# 6_Magnetorquer_Drivers.net
KiCad netlist of a schematic drawn in Altium Designer
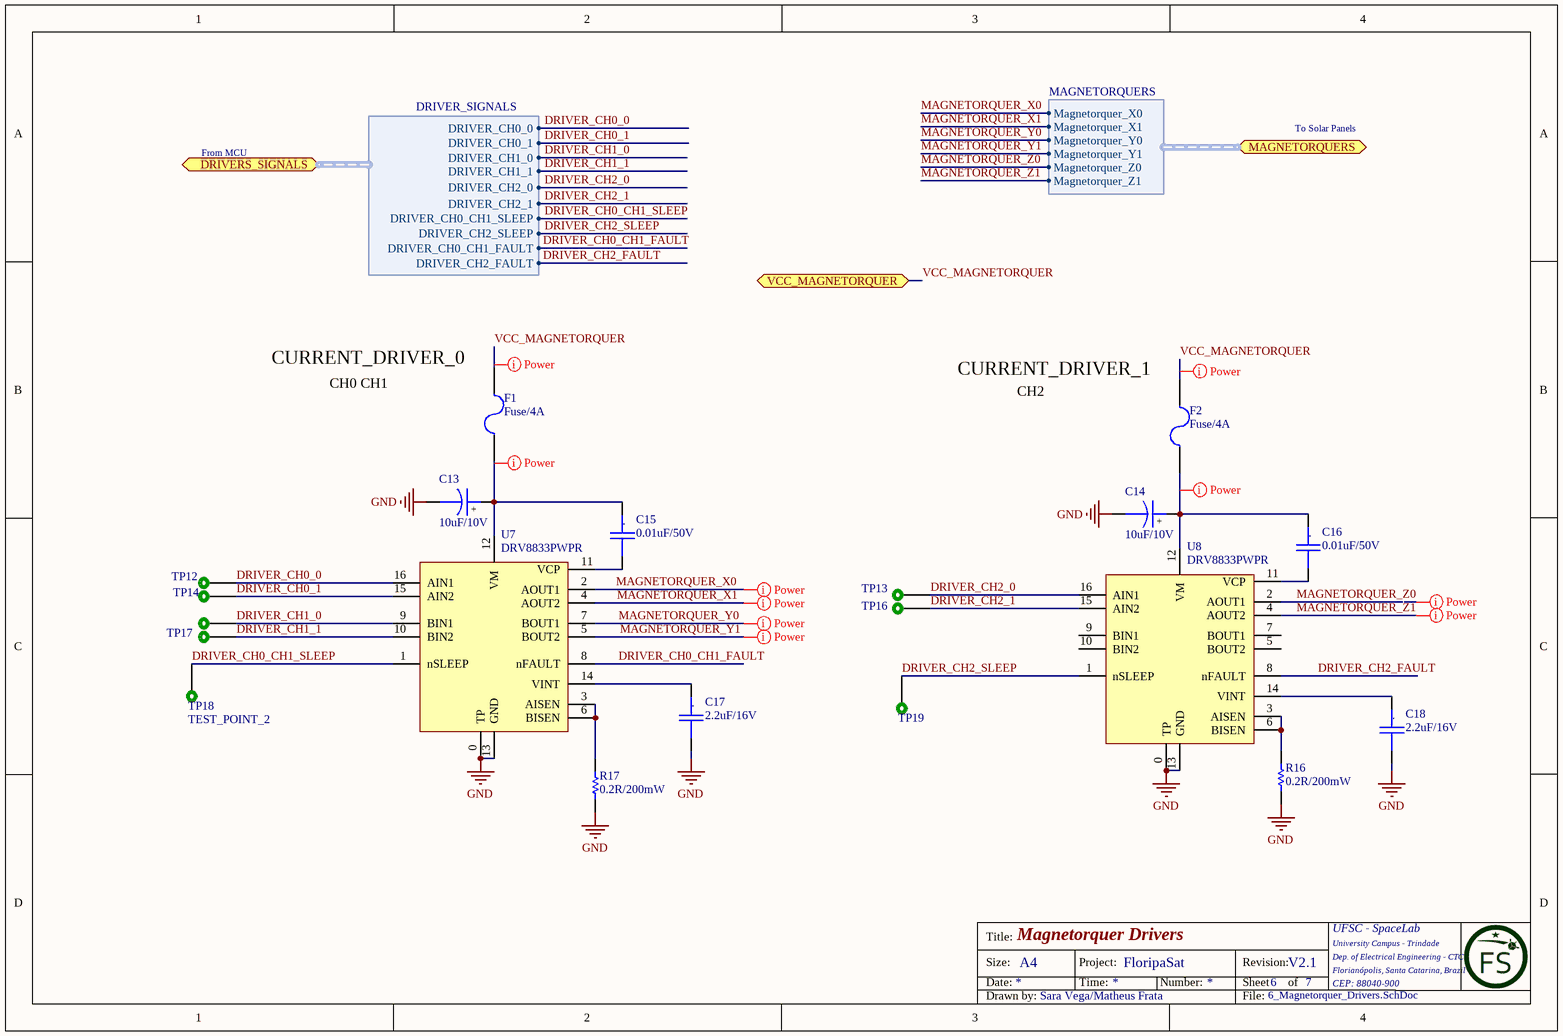
[diagram p0: 6_Magnetorquer_Drivers.SchDoc]

(export (version "E")
  (design (tool "Eeschema 10.0.6"))
  (components
    (comp (ref "C13")
      (value "10uF/10V")
      (footprint "FloripaSatPcbLib:CC0805_Tantalum")
      (description "CAP Tantalum 10uF 10V 20% 0805")
      (fields (field (name "PARTNUMBER") "TPSP106M010R2000"))
      (libsource (lib "FloripaSatSchlib") (part "Cap_Tant_SMD_10uF_10V_0805"))
    )
    (comp (ref "C14")
      (value "10uF/10V")
      (footprint "FloripaSatPcbLib:CC0805_Tantalum")
      (description "CAP Tantalum 10uF 10V 20% 0805")
      (fields (field (name "PARTNUMBER") "TPSP106M010R2000"))
      (libsource (lib "FloripaSatSchlib") (part "Cap_Tant_SMD_10uF_10V_0805"))
    )
    (comp (ref "C15")
      (value "0.01uF/50V")
      (footprint "CC0805")
      (description "CAP CER 0.01uF 50V 10% X7R 0805")
      (fields (field (name "PARTNUMBER") "CL21B103KAANNNC"))
      (libsource (lib "FloripaSatSchlib") (part "Cap_Cer_X7R_0.01uF_50V_0805"))
    )
    (comp (ref "C16")
      (value "0.01uF/50V")
      (footprint "CC0805")
      (description "CAP CER 0.01uF 50V 10% X7R 0805")
      (fields (field (name "PARTNUMBER") "CL21B103KAANNNC"))
      (libsource (lib "FloripaSatSchlib") (part "Cap_Cer_X7R_0.01uF_50V_0805"))
    )
    (comp (ref "C17")
      (value "2.2uF/16V")
      (footprint "CC0805")
      (description "CAP CER 2.2uF 16V 0805")
      (fields (field (name "PARTNUMBER") "C2012X7R1C225K125AB"))
      (libsource (lib "FloripaSatSchlib") (part "Cap_Cer_X7R_2.2uF_16V_0805"))
    )
    (comp (ref "C18")
      (value "2.2uF/16V")
      (footprint "CC0805")
      (description "CAP CER 2.2uF 16V 0805")
      (fields (field (name "PARTNUMBER") "C2012X7R1C225K125AB"))
      (libsource (lib "FloripaSatSchlib") (part "Cap_Cer_X7R_2.2uF_16V_0805"))
    )
    (comp (ref "F1")
      (value "Fuse/4A")
      (footprint "1206")
      (description "Surface Mount Fuses SMD FA 4A")
      (fields (field (name "PARTNUMBER") "0437.375WR") (field (name "PUBLISHER") "Altium Limited"))
      (libsource (lib "FloripaSatSchlib") (part "Fuse"))
    )
    (comp (ref "F2")
      (value "Fuse/4A")
      (footprint "1206")
      (description "Surface Mount Fuses SMD FA 4A")
      (fields (field (name "PARTNUMBER") "0437.375WR") (field (name "PUBLISHER") "Altium Limited"))
      (libsource (lib "FloripaSatSchlib") (part "Fuse"))
    )
    (comp (ref "R16")
      (value "0.2R/200mW")
      (footprint "FloripaSatPcbLib:0805")
      (description "RES 0.2 OHM -0.2W 1% 0805")
      (fields (field (name "PARTNUMBER") "RL1220S-R20-F"))
      (libsource (lib "FloripaSatSchlib") (part "R0.015R_1%_0.5W_0805"))
    )
    (comp (ref "R17")
      (value "0.2R/200mW")
      (footprint "FloripaSatPcbLib:0805")
      (description "RES 0.2 OHM - 0.2W 1% 0805")
      (fields (field (name "PARTNUMBER") "RL1220S-R20-F"))
      (libsource (lib "FloripaSatSchlib") (part "R0.015R_1%_0.5W_0805"))
    )
    (comp (ref "TP12")
      (value "TEST_POINT_2")
      (footprint "TEST_POINT_2")
      (description "Test point")
      (libsource (lib "FloripaSatSchlib") (part "TEST_POINT_2"))
    )
    (comp (ref "TP13")
      (value "TEST_POINT_2")
      (footprint "TEST_POINT_2")
      (description "Test point")
      (libsource (lib "FloripaSatSchlib") (part "TEST_POINT_2"))
    )
    (comp (ref "TP14")
      (value "TEST_POINT_2")
      (footprint "TEST_POINT_2")
      (description "Test point")
      (libsource (lib "FloripaSatSchlib") (part "TEST_POINT_2"))
    )
    (comp (ref "TP15")
      (value "TEST_POINT_2")
      (footprint "TEST_POINT_2")
      (description "Test point")
      (libsource (lib "FloripaSatSchlib") (part "TEST_POINT_2"))
    )
    (comp (ref "TP16")
      (value "TEST_POINT_2")
      (footprint "TEST_POINT_2")
      (description "Test point")
      (libsource (lib "FloripaSatSchlib") (part "TEST_POINT_2"))
    )
    (comp (ref "TP17")
      (value "TEST_POINT_2")
      (footprint "TEST_POINT_2")
      (description "Test point")
      (libsource (lib "FloripaSatSchlib") (part "TEST_POINT_2"))
    )
    (comp (ref "TP18")
      (value "TEST_POINT_2")
      (footprint "TEST_POINT_2")
      (description "Test point")
      (libsource (lib "FloripaSatSchlib") (part "TEST_POINT_2"))
    )
    (comp (ref "TP19")
      (value "TEST_POINT_2")
      (footprint "TEST_POINT_2")
      (description "Test point")
      (libsource (lib "FloripaSatSchlib") (part "TEST_POINT_2"))
    )
    (comp (ref "U7")
      (value "DRV8833PWPR")
      (footprint "16TTSSOP")
      (libsource (lib "FloripaSatSchlib") (part "DRV8833PWPR"))
    )
    (comp (ref "U8")
      (value "DRV8833PWPR")
      (footprint "16TTSSOP")
      (libsource (lib "FloripaSatSchlib") (part "DRV8833PWPR"))
    )
  )
  (nets
    (net (code "3") (name "/DRIVER_CH0_0") (class "Default")
      (node (ref "TP12") (pin "1") (pinfunction "1_1") (pintype "passive"))
      (node (ref "U7") (pin "16") (pinfunction "AIN1_16") (pintype "passive"))
    )
    (net (code "4") (name "/DRIVER_CH0_1") (class "Default")
      (node (ref "TP14") (pin "1") (pinfunction "1_1") (pintype "passive"))
      (node (ref "U7") (pin "15") (pinfunction "AIN2_15") (pintype "passive"))
    )
    (net (code "5") (name "/DRIVER_CH0_CH1_FAULT") (class "Default")
      (node (ref "U7") (pin "8") (pinfunction "nFAULT_8") (pintype "passive"))
    )
    (net (code "6") (name "/DRIVER_CH0_CH1_SLEEP") (class "Default")
      (node (ref "TP18") (pin "1") (pinfunction "1_1") (pintype "passive"))
      (node (ref "U7") (pin "1") (pinfunction "nSLEEP_1") (pintype "passive"))
    )
    (net (code "7") (name "/DRIVER_CH1_0") (class "Default")
      (node (ref "TP15") (pin "1") (pinfunction "1_1") (pintype "passive"))
      (node (ref "U7") (pin "9") (pinfunction "BIN1_9") (pintype "passive"))
    )
    (net (code "8") (name "/DRIVER_CH1_1") (class "Default")
      (node (ref "TP17") (pin "1") (pinfunction "1_1") (pintype "passive"))
      (node (ref "U7") (pin "10") (pinfunction "BIN2_10") (pintype "passive"))
    )
    (net (code "9") (name "/DRIVER_CH2_0") (class "Default")
      (node (ref "TP13") (pin "1") (pinfunction "1_1") (pintype "passive"))
      (node (ref "U8") (pin "16") (pinfunction "AIN1_16") (pintype "passive"))
    )
    (net (code "10") (name "/DRIVER_CH2_1") (class "Default")
      (node (ref "TP16") (pin "1") (pinfunction "1_1") (pintype "passive"))
      (node (ref "U8") (pin "15") (pinfunction "AIN2_15") (pintype "passive"))
    )
    (net (code "11") (name "/DRIVER_CH2_FAULT") (class "Default")
      (node (ref "U8") (pin "8") (pinfunction "nFAULT_8") (pintype "passive"))
    )
    (net (code "12") (name "/DRIVER_CH2_SLEEP") (class "Default")
      (node (ref "TP19") (pin "1") (pinfunction "1_1") (pintype "passive"))
      (node (ref "U8") (pin "1") (pinfunction "nSLEEP_1") (pintype "passive"))
    )
    (net (code "13") (name "/MAGNETORQUER_X0") (class "Default")
      (node (ref "U7") (pin "2") (pinfunction "AOUT1_2") (pintype "passive"))
    )
    (net (code "14") (name "/MAGNETORQUER_X1") (class "Default")
      (node (ref "U7") (pin "4") (pinfunction "AOUT2_4") (pintype "passive"))
    )
    (net (code "15") (name "/MAGNETORQUER_Y0") (class "Default")
      (node (ref "U7") (pin "7") (pinfunction "BOUT1_7") (pintype "passive"))
    )
    (net (code "16") (name "/MAGNETORQUER_Y1") (class "Default")
      (node (ref "U7") (pin "5") (pinfunction "BOUT2_5") (pintype "passive"))
    )
    (net (code "17") (name "/MAGNETORQUER_Z0") (class "Default")
      (node (ref "U8") (pin "2") (pinfunction "AOUT1_2") (pintype "passive"))
    )
    (net (code "18") (name "/MAGNETORQUER_Z1") (class "Default")
      (node (ref "U8") (pin "4") (pinfunction "AOUT2_4") (pintype "passive"))
    )
    (net (code "19") (name "/VCC_MAGNETORQUER") (class "Default")
      (node (ref "F1") (pin "2") (pinfunction "2_2") (pintype "passive"))
      (node (ref "F2") (pin "2") (pinfunction "2_2") (pintype "passive"))
    )
    (net (code "22") (name "GND") (class "Default")
      (node (ref "C13") (pin "2") (pinfunction "2_2") (pintype "passive"))
      (node (ref "C14") (pin "2") (pinfunction "2_2") (pintype "passive"))
      (node (ref "C17") (pin "2") (pinfunction "2_2") (pintype "passive"))
      (node (ref "C18") (pin "2") (pinfunction "2_2") (pintype "passive"))
      (node (ref "R16") (pin "1") (pinfunction "1_1") (pintype "passive"))
      (node (ref "R17") (pin "1") (pinfunction "1_1") (pintype "passive"))
      (node (ref "U7") (pin "0") (pinfunction "TP_0") (pintype "passive"))
      (node (ref "U7") (pin "13") (pinfunction "GND_13") (pintype "passive"))
      (node (ref "U8") (pin "0") (pinfunction "TP_0") (pintype "passive"))
      (node (ref "U8") (pin "13") (pinfunction "GND_13") (pintype "passive"))
    )
    (net (code "23") (name "Net-(U7-AISEN)") (class "Default")
      (node (ref "R17") (pin "2") (pinfunction "2_2") (pintype "passive"))
      (node (ref "U7") (pin "3") (pinfunction "AISEN_3") (pintype "passive"))
      (node (ref "U7") (pin "6") (pinfunction "BISEN_6") (pintype "passive"))
    )
    (net (code "24") (name "Net-(U7-VCP)") (class "Default")
      (node (ref "C15") (pin "2") (pinfunction "2_2") (pintype "passive"))
      (node (ref "U7") (pin "11") (pinfunction "VCP_11") (pintype "passive"))
    )
    (net (code "25") (name "Net-(U7-VINT)") (class "Default")
      (node (ref "C17") (pin "1") (pinfunction "1_1") (pintype "passive"))
      (node (ref "U7") (pin "14") (pinfunction "VINT_14") (pintype "passive"))
    )
    (net (code "26") (name "Net-(U7-VM)") (class "Default")
      (node (ref "C13") (pin "1") (pinfunction "1_1") (pintype "passive"))
      (node (ref "C15") (pin "1") (pinfunction "1_1") (pintype "passive"))
      (node (ref "F1") (pin "1") (pinfunction "1_1") (pintype "passive"))
      (node (ref "U7") (pin "12") (pinfunction "VM_12") (pintype "passive"))
    )
    (net (code "27") (name "Net-(U8-AISEN)") (class "Default")
      (node (ref "R16") (pin "2") (pinfunction "2_2") (pintype "passive"))
      (node (ref "U8") (pin "3") (pinfunction "AISEN_3") (pintype "passive"))
      (node (ref "U8") (pin "6") (pinfunction "BISEN_6") (pintype "passive"))
    )
    (net (code "28") (name "Net-(U8-VCP)") (class "Default")
      (node (ref "C16") (pin "2") (pinfunction "2_2") (pintype "passive"))
      (node (ref "U8") (pin "11") (pinfunction "VCP_11") (pintype "passive"))
    )
    (net (code "29") (name "Net-(U8-VINT)") (class "Default")
      (node (ref "C18") (pin "1") (pinfunction "1_1") (pintype "passive"))
      (node (ref "U8") (pin "14") (pinfunction "VINT_14") (pintype "passive"))
    )
    (net (code "30") (name "Net-(U8-VM)") (class "Default")
      (node (ref "C14") (pin "1") (pinfunction "1_1") (pintype "passive"))
      (node (ref "C16") (pin "1") (pinfunction "1_1") (pintype "passive"))
      (node (ref "F2") (pin "1") (pinfunction "1_1") (pintype "passive"))
      (node (ref "U8") (pin "12") (pinfunction "VM_12") (pintype "passive"))
    )
    (net (code "31") (name "unconnected-(U8-BIN1-Pad9)") (class "Default")
      (node (ref "U8") (pin "9") (pinfunction "BIN1_9") (pintype "passive"))
    )
    (net (code "32") (name "unconnected-(U8-BIN2-Pad10)") (class "Default")
      (node (ref "U8") (pin "10") (pinfunction "BIN2_10") (pintype "passive"))
    )
    (net (code "33") (name "unconnected-(U8-BOUT1-Pad7)") (class "Default")
      (node (ref "U8") (pin "7") (pinfunction "BOUT1_7") (pintype "passive"))
    )
    (net (code "34") (name "unconnected-(U8-BOUT2-Pad5)") (class "Default")
      (node (ref "U8") (pin "5") (pinfunction "BOUT2_5") (pintype "passive"))
    )
  )
)
